# V3S.net
KiCad netlist of a schematic drawn in Altium Designer
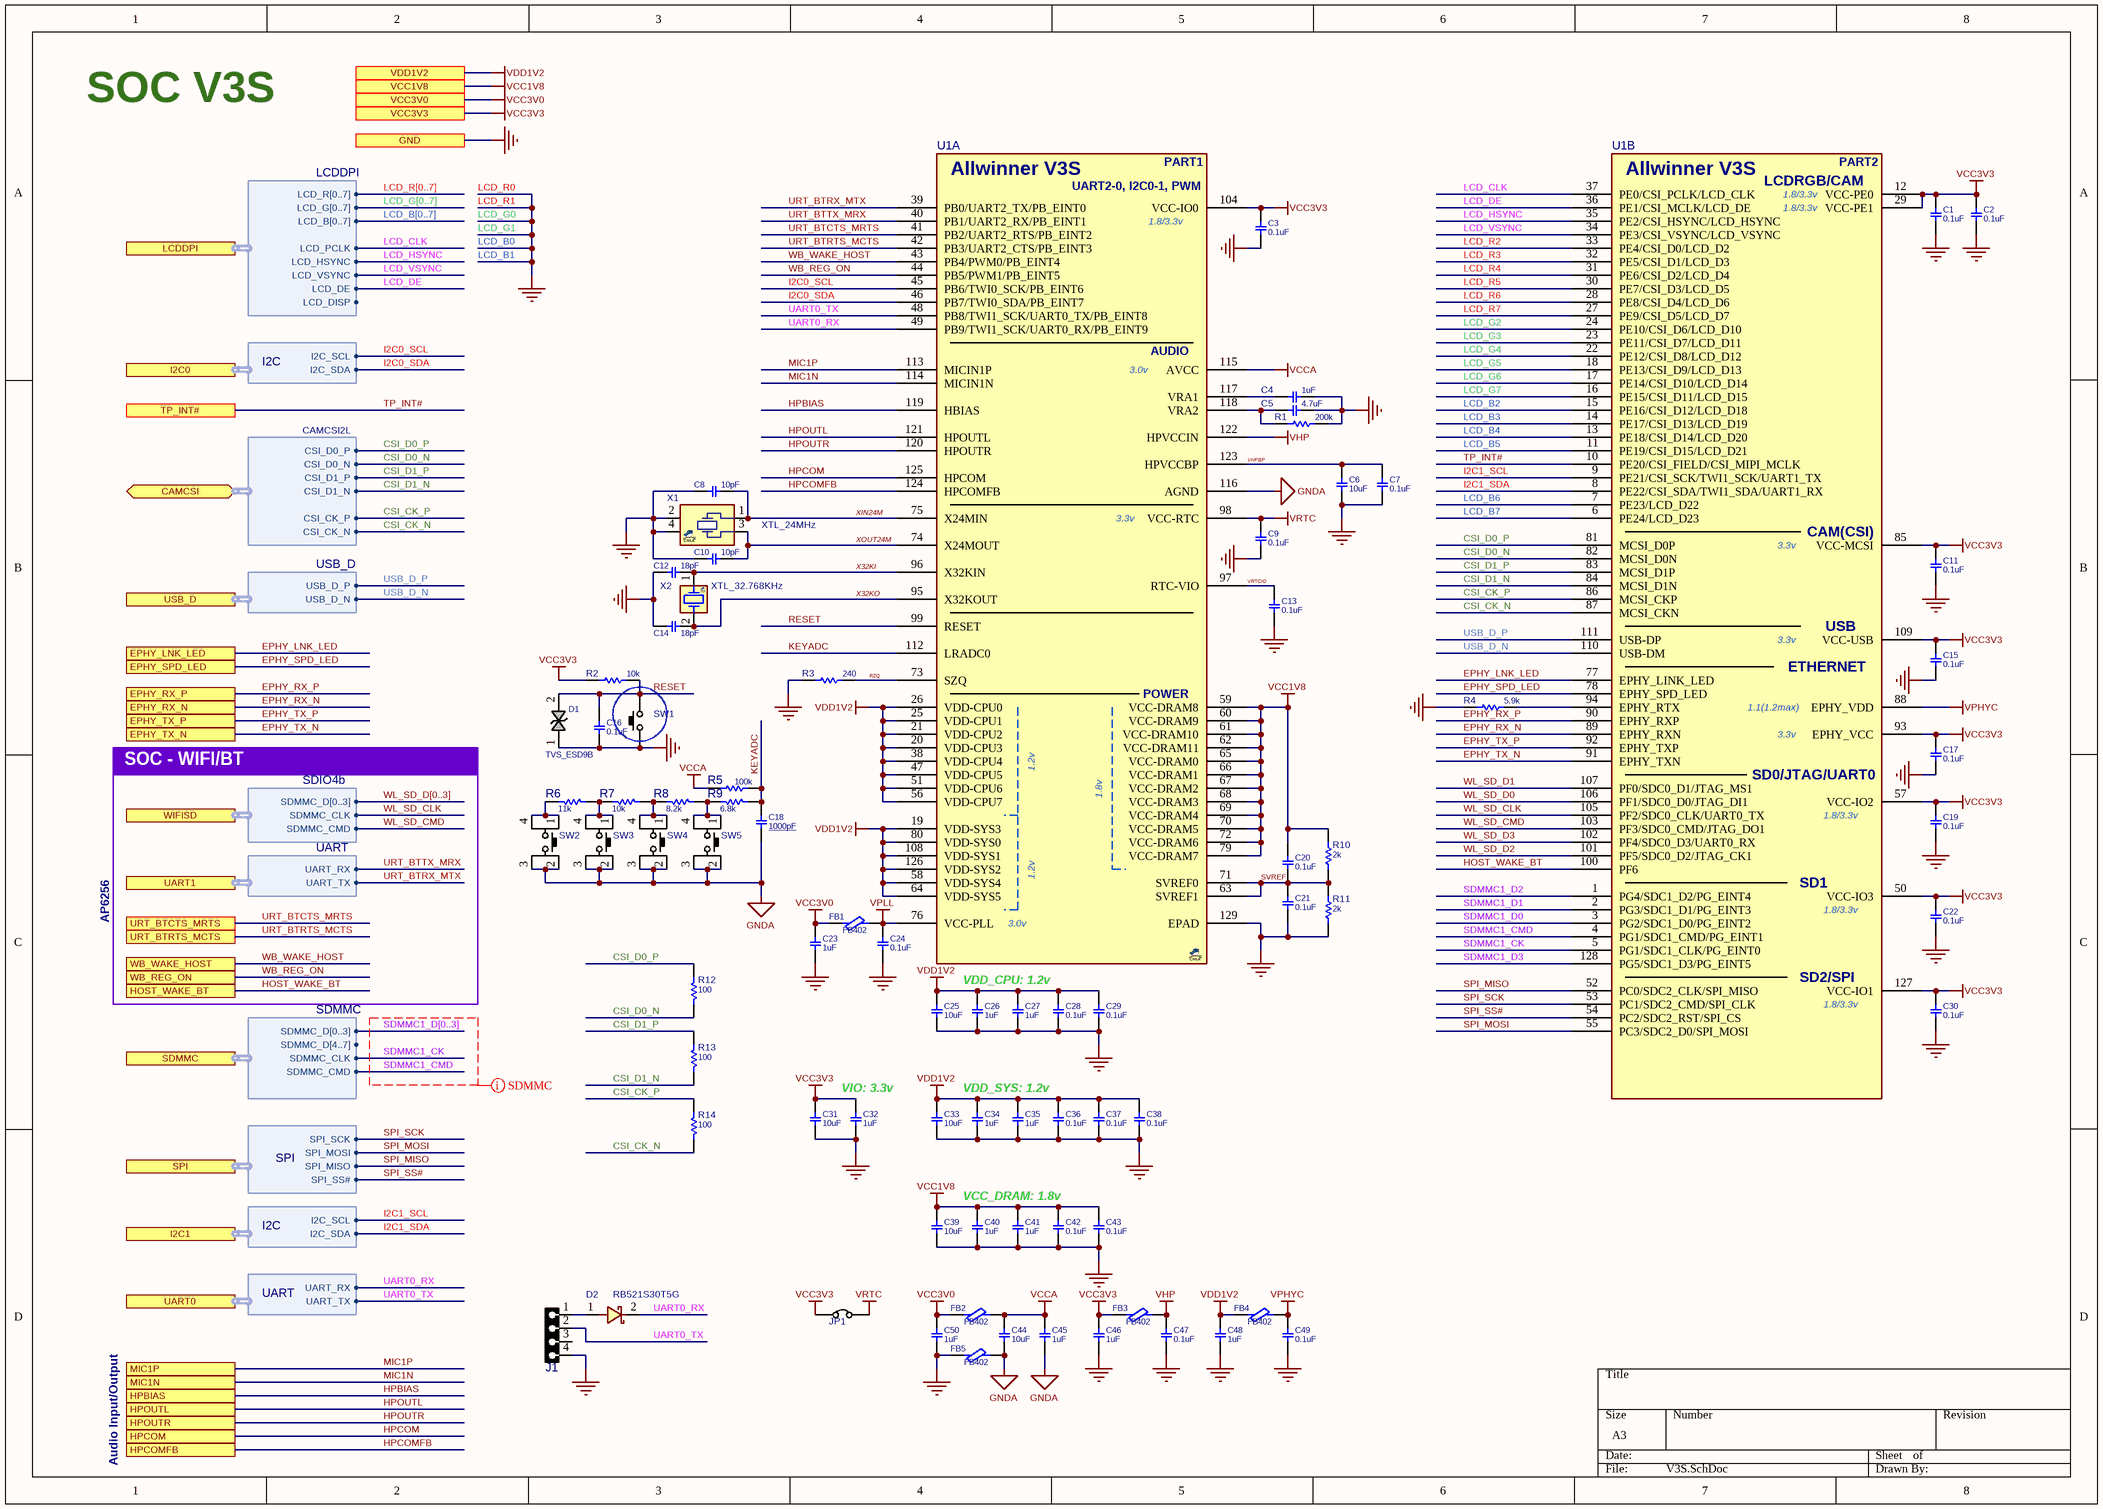
[diagram p0: V3S.SchDoc]

(export (version "E")
  (design (tool "Eeschema 10.0.6"))
  (components
    (comp (ref "C1")
      (value "0.1uF")
      (footprint "C0402")
      (description "CAP, MLCC")
      (fields (field (name "MANF_P#") "GRM155R71H104KE14D") (field (name "MANF") "Murata"))
      (libsource (lib "passive_smd") (part "CAP_SMD_MLCC"))
    )
    (comp (ref "C2")
      (value "0.1uF")
      (footprint "C0402")
      (description "CAP, MLCC")
      (fields (field (name "MANF_P#") "GRM155R71H104KE14D") (field (name "MANF") "Murata"))
      (libsource (lib "passive_smd") (part "CAP_SMD_MLCC"))
    )
    (comp (ref "C3")
      (value "0.1uF")
      (footprint "C0402")
      (description "CAP, MLCC")
      (fields (field (name "MANF_P#") "GRM155R71H104KE14D") (field (name "MANF") "Murata"))
      (libsource (lib "passive_smd") (part "CAP_SMD_MLCC"))
    )
    (comp (ref "C4")
      (value "1uF")
      (footprint "C0402")
      (description "CAP, MLCC")
      (fields (field (name "MANF_P#") "GMK105ABJ105KV-F") (field (name "MANF") "Taiyo Yuden"))
      (libsource (lib "passive_smd") (part "CAP_SMD_MLCC"))
    )
    (comp (ref "C5")
      (value "4.7uF")
      (footprint "C0402")
      (description "CAP, MLCC")
      (fields (field (name "MANF_P#") "LMK105BBJ475MVLF") (field (name "MANF") "Taiyo Yuden"))
      (libsource (lib "passive_smd") (part "CAP_SMD_MLCC"))
    )
    (comp (ref "C6")
      (value "10uF")
      (footprint "C0402")
      (description "CAP, MLCC")
      (fields (field (name "MANF_P#") "GRM155R60J106ME15") (field (name "MANF") "Murata"))
      (libsource (lib "mlcc_smd_passive") (part "CAP_SMD_MLCC"))
    )
    (comp (ref "C7")
      (value "0.1uF")
      (footprint "C0402")
      (description "CAP, MLCC")
      (fields (field (name "MANF_P#") "GRM155R71H104KE14D") (field (name "MANF") "Murata"))
      (libsource (lib "passive_smd") (part "CAP_SMD_MLCC"))
    )
    (comp (ref "C8")
      (value "10pF")
      (footprint "C0402")
      (description "CAP, MLCC")
      (fields (field (name "MANF_P#") "CC0402JRNPO9BN180") (field (name "MANF") "Yageo"))
      (libsource (lib "mlcc_smd_passive") (part "CAP_SMD_MLCC"))
    )
    (comp (ref "C9")
      (value "0.1uF")
      (footprint "C0402")
      (description "CAP, MLCC")
      (fields (field (name "MANF_P#") "GRM155R71H104KE14D") (field (name "MANF") "Murata"))
      (libsource (lib "passive_smd") (part "CAP_SMD_MLCC"))
    )
    (comp (ref "C10")
      (value "10pF")
      (footprint "C0402")
      (description "CAP, MLCC")
      (fields (field (name "MANF_P#") "CC0402JRNPO9BN180") (field (name "MANF") "Yageo"))
      (libsource (lib "mlcc_smd_passive") (part "CAP_SMD_MLCC"))
    )
    (comp (ref "C11")
      (value "0.1uF")
      (footprint "C0402")
      (description "CAP, MLCC")
      (fields (field (name "MANF_P#") "GRM155R71H104KE14D") (field (name "MANF") "Murata"))
      (libsource (lib "passive_smd") (part "CAP_SMD_MLCC"))
    )
    (comp (ref "C12")
      (value "18pF")
      (footprint "C0402")
      (description "CAP, MLCC")
      (fields (field (name "MANF_P#") "CC0402CRNPO9BN3R3") (field (name "MANF") "YAGEO"))
      (libsource (lib "passive_smd") (part "CAP_SMD_MLCC"))
    )
    (comp (ref "C13")
      (value "0.1uF")
      (footprint "C0402")
      (description "CAP, MLCC")
      (fields (field (name "MANF_P#") "GRM155R71H104KE14D") (field (name "MANF") "Murata"))
      (libsource (lib "passive_smd") (part "CAP_SMD_MLCC"))
    )
    (comp (ref "C14")
      (value "18pF")
      (footprint "C0402")
      (description "CAP, MLCC")
      (fields (field (name "MANF_P#") "CC0402CRNPO9BN3R3") (field (name "MANF") "YAGEO"))
      (libsource (lib "passive_smd") (part "CAP_SMD_MLCC"))
    )
    (comp (ref "C15")
      (value "0.1uF")
      (footprint "C0402")
      (description "CAP, MLCC")
      (fields (field (name "MANF_P#") "GRM155R71H104KE14D") (field (name "MANF") "Murata"))
      (libsource (lib "passive_smd") (part "CAP_SMD_MLCC"))
    )
    (comp (ref "C16")
      (value "0.1uF")
      (footprint "C0402")
      (description "CAP, MLCC")
      (fields (field (name "MANF_P#") "CL03A104KP3NNWC") (field (name "MANF") "Samsung"))
      (libsource (lib "passive_smd") (part "CAP_SMD_MLCC"))
    )
    (comp (ref "C17")
      (value "0.1uF")
      (footprint "C0402")
      (description "CAP, MLCC")
      (fields (field (name "MANF_P#") "GRM155R71H104KE14D") (field (name "MANF") "Murata"))
      (libsource (lib "passive_smd") (part "CAP_SMD_MLCC"))
    )
    (comp (ref "C18")
      (value "1000pF")
      (footprint "C0402")
      (description "CAP, MLCC")
      (fields (field (name "MANF_P#") "MANF_PART#"))
      (libsource (lib "passive_smd") (part "CAP_SMD_MLCC_0603"))
    )
    (comp (ref "C19")
      (value "0.1uF")
      (footprint "C0402")
      (description "CAP, MLCC")
      (fields (field (name "MANF_P#") "GRM155R71H104KE14D") (field (name "MANF") "Murata"))
      (libsource (lib "passive_smd") (part "CAP_SMD_MLCC"))
    )
    (comp (ref "C20")
      (value "0.1uF")
      (footprint "C0402")
      (description "CAP, MLCC")
      (fields (field (name "MANF_P#") "GRM155R71H104KE14D") (field (name "MANF") "Murata"))
      (libsource (lib "passive_smd") (part "CAP_SMD_MLCC"))
    )
    (comp (ref "C21")
      (value "0.1uF")
      (footprint "C0402")
      (description "CAP, MLCC")
      (fields (field (name "MANF_P#") "GRM155R71H104KE14D") (field (name "MANF") "Murata"))
      (libsource (lib "passive_smd") (part "CAP_SMD_MLCC"))
    )
    (comp (ref "C22")
      (value "0.1uF")
      (footprint "C0402")
      (description "CAP, MLCC")
      (fields (field (name "MANF_P#") "GRM155R71H104KE14D") (field (name "MANF") "Murata"))
      (libsource (lib "passive_smd") (part "CAP_SMD_MLCC"))
    )
    (comp (ref "C23")
      (value "1uF")
      (footprint "C0402")
      (description "CAP, MLCC")
      (fields (field (name "MANF_P#") "GMK105ABJ105KV-F") (field (name "MANF") "Taiyo Yuden"))
      (libsource (lib "passive_smd") (part "CAP_SMD_MLCC"))
    )
    (comp (ref "C24")
      (value "0.1uF")
      (footprint "C0402")
      (description "CAP, MLCC")
      (fields (field (name "MANF_P#") "GRM155R71H104KE14D") (field (name "MANF") "Murata"))
      (libsource (lib "passive_smd") (part "CAP_SMD_MLCC"))
    )
    (comp (ref "C25")
      (value "10uF")
      (footprint "C0402")
      (description "CAP, MLCC")
      (fields (field (name "MANF_P#") "GRM155R60J106ME15") (field (name "MANF") "Murata"))
      (libsource (lib "mlcc_smd_passive") (part "CAP_SMD_MLCC"))
    )
    (comp (ref "C26")
      (value "1uF")
      (footprint "C0402")
      (description "CAP, MLCC")
      (fields (field (name "MANF_P#") "GMK105ABJ105KV-F") (field (name "MANF") "Taiyo Yuden"))
      (libsource (lib "passive_smd") (part "CAP_SMD_MLCC"))
    )
    (comp (ref "C27")
      (value "1uF")
      (footprint "C0402")
      (description "CAP, MLCC")
      (fields (field (name "MANF_P#") "GMK105ABJ105KV-F") (field (name "MANF") "Taiyo Yuden"))
      (libsource (lib "passive_smd") (part "CAP_SMD_MLCC"))
    )
    (comp (ref "C28")
      (value "0.1uF")
      (footprint "C0402")
      (description "CAP, MLCC")
      (fields (field (name "MANF_P#") "GRM155R71H104KE14D") (field (name "MANF") "Murata"))
      (libsource (lib "passive_smd") (part "CAP_SMD_MLCC"))
    )
    (comp (ref "C29")
      (value "0.1uF")
      (footprint "C0402")
      (description "CAP, MLCC")
      (fields (field (name "MANF_P#") "GRM155R71H104KE14D") (field (name "MANF") "Murata"))
      (libsource (lib "passive_smd") (part "CAP_SMD_MLCC"))
    )
    (comp (ref "C30")
      (value "0.1uF")
      (footprint "C0402")
      (description "CAP, MLCC")
      (fields (field (name "MANF_P#") "GRM155R71H104KE14D") (field (name "MANF") "Murata"))
      (libsource (lib "passive_smd") (part "CAP_SMD_MLCC"))
    )
    (comp (ref "C31")
      (value "10uF")
      (footprint "C0402")
      (description "CAP, MLCC")
      (fields (field (name "MANF_P#") "GRM155R60J106ME15") (field (name "MANF") "Murata"))
      (libsource (lib "mlcc_smd_passive") (part "CAP_SMD_MLCC"))
    )
    (comp (ref "C32")
      (value "1uF")
      (footprint "C0402")
      (description "CAP, MLCC")
      (fields (field (name "MANF_P#") "GMK105ABJ105KV-F") (field (name "MANF") "Taiyo Yuden"))
      (libsource (lib "passive_smd") (part "CAP_SMD_MLCC"))
    )
    (comp (ref "C33")
      (value "10uF")
      (footprint "C0402")
      (description "CAP, MLCC")
      (fields (field (name "MANF_P#") "GRM155R60J106ME15") (field (name "MANF") "Murata"))
      (libsource (lib "mlcc_smd_passive") (part "CAP_SMD_MLCC"))
    )
    (comp (ref "C34")
      (value "1uF")
      (footprint "C0402")
      (description "CAP, MLCC")
      (fields (field (name "MANF_P#") "GMK105ABJ105KV-F") (field (name "MANF") "Taiyo Yuden"))
      (libsource (lib "passive_smd") (part "CAP_SMD_MLCC"))
    )
    (comp (ref "C35")
      (value "1uF")
      (footprint "C0402")
      (description "CAP, MLCC")
      (fields (field (name "MANF_P#") "GMK105ABJ105KV-F") (field (name "MANF") "Taiyo Yuden"))
      (libsource (lib "passive_smd") (part "CAP_SMD_MLCC"))
    )
    (comp (ref "C36")
      (value "0.1uF")
      (footprint "C0402")
      (description "CAP, MLCC")
      (fields (field (name "MANF_P#") "GRM155R71H104KE14D") (field (name "MANF") "Murata"))
      (libsource (lib "passive_smd") (part "CAP_SMD_MLCC"))
    )
    (comp (ref "C37")
      (value "0.1uF")
      (footprint "C0402")
      (description "CAP, MLCC")
      (fields (field (name "MANF_P#") "GRM155R71H104KE14D") (field (name "MANF") "Murata"))
      (libsource (lib "passive_smd") (part "CAP_SMD_MLCC"))
    )
    (comp (ref "C38")
      (value "0.1uF")
      (footprint "C0402")
      (description "CAP, MLCC")
      (fields (field (name "MANF_P#") "GRM155R71H104KE14D") (field (name "MANF") "Murata"))
      (libsource (lib "passive_smd") (part "CAP_SMD_MLCC"))
    )
    (comp (ref "C39")
      (value "10uF")
      (footprint "C0402")
      (description "CAP, MLCC")
      (fields (field (name "MANF_P#") "GRM155R60J106ME15") (field (name "MANF") "Murata"))
      (libsource (lib "mlcc_smd_passive") (part "CAP_SMD_MLCC"))
    )
    (comp (ref "C40")
      (value "1uF")
      (footprint "C0402")
      (description "CAP, MLCC")
      (fields (field (name "MANF_P#") "GMK105ABJ105KV-F") (field (name "MANF") "Taiyo Yuden"))
      (libsource (lib "passive_smd") (part "CAP_SMD_MLCC"))
    )
    (comp (ref "C41")
      (value "1uF")
      (footprint "C0402")
      (description "CAP, MLCC")
      (fields (field (name "MANF_P#") "GMK105ABJ105KV-F") (field (name "MANF") "Taiyo Yuden"))
      (libsource (lib "passive_smd") (part "CAP_SMD_MLCC"))
    )
    (comp (ref "C42")
      (value "0.1uF")
      (footprint "C0402")
      (description "CAP, MLCC")
      (fields (field (name "MANF_P#") "GRM155R71H104KE14D") (field (name "MANF") "Murata"))
      (libsource (lib "passive_smd") (part "CAP_SMD_MLCC"))
    )
    (comp (ref "C43")
      (value "0.1uF")
      (footprint "C0402")
      (description "CAP, MLCC")
      (fields (field (name "MANF_P#") "GRM155R71H104KE14D") (field (name "MANF") "Murata"))
      (libsource (lib "passive_smd") (part "CAP_SMD_MLCC"))
    )
    (comp (ref "C44")
      (value "10uF")
      (footprint "C0402")
      (description "CAP, MLCC")
      (fields (field (name "MANF_P#") "GRM155R60J106ME15") (field (name "MANF") "Murata"))
      (libsource (lib "mlcc_smd_passive") (part "CAP_SMD_MLCC"))
    )
    (comp (ref "C45")
      (value "1uF")
      (footprint "C0402")
      (description "CAP, MLCC")
      (fields (field (name "MANF_P#") "GMK105ABJ105KV-F") (field (name "MANF") "Taiyo Yuden"))
      (libsource (lib "passive_smd") (part "CAP_SMD_MLCC"))
    )
    (comp (ref "C46")
      (value "1uF")
      (footprint "C0402")
      (description "CAP, MLCC")
      (fields (field (name "MANF_P#") "GMK105ABJ105KV-F") (field (name "MANF") "Taiyo Yuden"))
      (libsource (lib "passive_smd") (part "CAP_SMD_MLCC"))
    )
    (comp (ref "C47")
      (value "0.1uF")
      (footprint "C0402")
      (description "CAP, MLCC")
      (fields (field (name "MANF_P#") "GRM155R71H104KE14D") (field (name "MANF") "Murata"))
      (libsource (lib "passive_smd") (part "CAP_SMD_MLCC"))
    )
    (comp (ref "C48")
      (value "1uF")
      (footprint "C0402")
      (description "CAP, MLCC")
      (fields (field (name "MANF_P#") "GMK105ABJ105KV-F") (field (name "MANF") "Taiyo Yuden"))
      (libsource (lib "passive_smd") (part "CAP_SMD_MLCC"))
    )
    (comp (ref "C49")
      (value "0.1uF")
      (footprint "C0402")
      (description "CAP, MLCC")
      (fields (field (name "MANF_P#") "GRM155R71H104KE14D") (field (name "MANF") "Murata"))
      (libsource (lib "passive_smd") (part "CAP_SMD_MLCC"))
    )
    (comp (ref "C50")
      (value "1uF")
      (footprint "C0402")
      (description "CAP, MLCC")
      (fields (field (name "MANF_P#") "GMK105ABJ105KV-F") (field (name "MANF") "Taiyo Yuden"))
      (libsource (lib "passive_smd") (part "CAP_SMD_MLCC"))
    )
    (comp (ref "D1")
      (value "TVS_ESD9B")
      (footprint "D_SOD923")
      (description "TVS, ESD PROTECT, Bidirectional")
      (fields (field (name "MANF_P#") "ESD9B3.3ST5G") (field (name "MANF") "ON"))
      (libsource (lib "protect_tvs_esd_fuse") (part "TVS_ESD9B3.3"))
    )
    (comp (ref "D2")
      (value "RB521S30T5G")
      (footprint "D_SOD523")
      (description "DIODE, SCHOTTKY")
      (fields (field (name "MANF") "DIODES"))
      (libsource (lib "diode") (part "DIODE_SMD_SCHOTTKY_1N5819"))
    )
    (comp (ref "FB1")
      (value "FB402")
      (footprint "L0402")
      (description "FERRITE_Bead, 0402, 0.5A, 200mOhm, 120@100MHz")
      (fields (field (name "MANF") "MURATA") (field (name "MANF_P#") "BLM15AG121SN1D"))
      (libsource (lib "emi_filter") (part "FBEAD_SMD_BLM15PD121"))
    )
    (comp (ref "FB2")
      (value "FB402")
      (footprint "L0402")
      (description "FERRITE_Bead, 0402, 0.5A, 200mOhm, 120@100MHz")
      (fields (field (name "MANF") "MURATA") (field (name "MANF_P#") "BLM15AG121SN1D"))
      (libsource (lib "emi_filter") (part "FBEAD_SMD_BLM15PD121"))
    )
    (comp (ref "FB3")
      (value "FB402")
      (footprint "L0402")
      (description "FERRITE_Bead, 0402, 0.5A, 200mOhm, 120@100MHz")
      (fields (field (name "MANF") "MURATA") (field (name "MANF_P#") "BLM15AG121SN1D"))
      (libsource (lib "emi_filter") (part "FBEAD_SMD_BLM15PD121"))
    )
    (comp (ref "FB4")
      (value "FB402")
      (footprint "L0402")
      (description "FERRITE_Bead, 0402, 0.5A, 200mOhm, 120@100MHz")
      (fields (field (name "MANF") "MURATA") (field (name "MANF_P#") "BLM15AG121SN1D"))
      (libsource (lib "emi_filter") (part "FBEAD_SMD_BLM15PD121"))
    )
    (comp (ref "FB5")
      (value "FB402")
      (footprint "L0402")
      (description "FERRITE_Bead, 0402, 0.5A, 200mOhm, 120@100MHz")
      (fields (field (name "MANF") "MURATA") (field (name "MANF_P#") "BLM15AG121SN1D"))
      (libsource (lib "emi_filter") (part "FBEAD_SMD_BLM15PD121"))
    )
    (comp (ref "J1")
      (value "HDR1X4")
      (footprint "HDR127MAG_4")
      (description "CONN, HEADER, Female, pitch: 1.27mm, 4POS")
      (libsource (lib "conn_header_1.27mm_st") (part "HDRMINI_F_1X4"))
    )
    (comp (ref "JP1")
      (value "JMPSOLDER")
      (footprint "JP_60X100")
      (description "JUMPER, HEADER 2PIN")
      (fields (field (name "MANF") "MANF") (field (name "MANF_P#") "MANF_P#"))
      (libsource (lib "test-tp_jumper") (part "JUMPER_SOLDER"))
    )
    (comp (ref "R1")
      (value "200k")
      (footprint "R0402")
      (description "RESISTOR, SMD")
      (libsource (lib "passive_res_smd") (part "RES_SMD"))
    )
    (comp (ref "R2")
      (value "10k")
      (footprint "R0402")
      (description "RESISTOR, SMD")
      (libsource (lib "passive_res_smd") (part "RES_SMD"))
    )
    (comp (ref "R3")
      (value "240")
      (footprint "R0402")
      (description "RESISTOR, SMD")
      (libsource (lib "passive_res_smd") (part "RES_SMD"))
    )
    (comp (ref "R4")
      (value "5.9k")
      (footprint "R0402")
      (description "RESISTOR, SMD")
      (libsource (lib "passive_res_smd") (part "RES_SMD"))
    )
    (comp (ref "R5")
      (value "100k")
      (footprint "R0402")
      (description "RESISTOR, SMD")
      (libsource (lib "passive_smd") (part "RES_SMD_0603"))
    )
    (comp (ref "R6")
      (value "11k")
      (footprint "R0402")
      (description "RESISTOR, SMD")
      (libsource (lib "passive_smd") (part "RES_SMD_0603"))
    )
    (comp (ref "R7")
      (value "10k")
      (footprint "R0402")
      (description "RESISTOR, SMD")
      (libsource (lib "passive_smd") (part "RES_SMD_0603"))
    )
    (comp (ref "R8")
      (value "8.2k")
      (footprint "R0402")
      (description "RESISTOR, SMD")
      (libsource (lib "passive_smd") (part "RES_SMD_0603"))
    )
    (comp (ref "R9")
      (value "6.8k")
      (footprint "R0402")
      (description "RESISTOR, SMD")
      (libsource (lib "passive_smd") (part "RES_SMD_0603"))
    )
    (comp (ref "R10")
      (value "2k")
      (footprint "R0402")
      (description "RESISTOR, SMD")
      (libsource (lib "passive_res_smd") (part "RES_SMD"))
    )
    (comp (ref "R11")
      (value "2k")
      (footprint "R0402")
      (description "RESISTOR, SMD")
      (libsource (lib "passive_res_smd") (part "RES_SMD"))
    )
    (comp (ref "R12")
      (value "100")
      (footprint "R0402")
      (description "RESISTOR, SMD")
      (libsource (lib "passive_res_smd") (part "RES_SMD"))
    )
    (comp (ref "R13")
      (value "100")
      (footprint "R0402")
      (description "RESISTOR, SMD")
      (libsource (lib "passive_res_smd") (part "RES_SMD"))
    )
    (comp (ref "R14")
      (value "100")
      (footprint "R0402")
      (description "RESISTOR, SMD")
      (libsource (lib "passive_res_smd") (part "RES_SMD"))
    )
    (comp (ref "SW1")
      (value "PUSHBUTTON")
      (footprint "SWPBS_SPST_3X2X1")
      (description "SWITCH, PUSH BUTTON, TACTILE, SMD, SPST, 3X2.5X1.2mm")
      (fields (field (name "MANF") "OMRON") (field (name "MANF_P#") "B3U-1000P"))
      (libsource (lib "switch_tact_PUSHB") (part "SWPBS_SPST_3X2_B3U-1000P"))
    )
    (comp (ref "SW2")
      (value "PUSHBUTTON")
      (footprint "SWPBS_SPDT_R_KMS")
      (description "SWITCH, PUSH BUTTON, TACTILE, THD, SPDT, RIGHT")
      (libsource (lib "switch_tact_PUSHB") (part "SWPBS_SPDT_R_CK"))
    )
    (comp (ref "SW3")
      (value "PUSHBUTTON")
      (footprint "SWPBS_SPDT_R_KMS")
      (description "SWITCH, PUSH BUTTON, TACTILE, THD, SPDT, RIGHT")
      (libsource (lib "switch_tact_PUSHB") (part "SWPBS_SPDT_R_CK"))
    )
    (comp (ref "SW4")
      (value "PUSHBUTTON")
      (footprint "SWPBS_SPDT_R_KMS")
      (description "SWITCH, PUSH BUTTON, TACTILE, THD, SPDT, RIGHT")
      (libsource (lib "switch_tact_PUSHB") (part "SWPBS_SPDT_R_CK"))
    )
    (comp (ref "SW5")
      (value "PUSHBUTTON")
      (footprint "SWPBS_SPDT_R_KMS")
      (description "SWITCH, PUSH BUTTON, TACTILE, THD, SPDT, RIGHT")
      (libsource (lib "switch_tact_PUSHB") (part "SWPBS_SPDT_R_CK"))
    )
    (comp (ref "U1")
      (value "Allwinner V3s")
      (footprint "QFG40_128T")
      (description "processor, Cortex-A7 1.2GHz w 512Mb DDR2")
      (fields (field (name "MANF") "Allwinner") (field (name "MANF_P#") "V3s"))
      (libsource (lib "processor_allwinner") (part "V3S_QFP128"))
    )
    (comp (ref "X1")
      (value "XTL_24MHz")
      (footprint "XTL_4_2016")
      (description "CRYSTAL")
      (fields (field (name "MANF") "Murata"))
      (libsource (lib "crystal") (part "XTL_4_40MHz_3225A"))
    )
    (comp (ref "X2")
      (value "XTL_32.768KHz")
      (footprint "XTL_2_1610")
      (description "Crystal")
      (fields (field (name "MANF_P#") "ABS05-32.768KHZ-9-T"))
      (libsource (lib "crystal") (part "XTL_2_32.768_3215A"))
    )
  )
  (nets
    (net (code "9") (name "/CSI_CK_N") (class "Default")
      (node (ref "R14") (pin "1") (pinfunction "1_1") (pintype "passive"))
      (node (ref "U1") (pin "87") (pinfunction "MCSI_CKN_87") (pintype "passive"))
    )
    (net (code "10") (name "/CSI_CK_P") (class "Default")
      (node (ref "R14") (pin "2") (pinfunction "2_2") (pintype "passive"))
      (node (ref "U1") (pin "86") (pinfunction "MCSI_CKP_86") (pintype "passive"))
    )
    (net (code "11") (name "/CSI_D0_N") (class "Default")
      (node (ref "R12") (pin "1") (pinfunction "1_1") (pintype "passive"))
      (node (ref "U1") (pin "82") (pinfunction "MCSI_D0N_82") (pintype "passive"))
    )
    (net (code "12") (name "/CSI_D0_P") (class "Default")
      (node (ref "R12") (pin "2") (pinfunction "2_2") (pintype "passive"))
      (node (ref "U1") (pin "81") (pinfunction "MCSI_D0P_81") (pintype "passive"))
    )
    (net (code "13") (name "/CSI_D1_N") (class "Default")
      (node (ref "R13") (pin "1") (pinfunction "1_1") (pintype "passive"))
      (node (ref "U1") (pin "84") (pinfunction "MCSI_D1N_84") (pintype "passive"))
    )
    (net (code "14") (name "/CSI_D1_P") (class "Default")
      (node (ref "R13") (pin "2") (pinfunction "2_2") (pintype "passive"))
      (node (ref "U1") (pin "83") (pinfunction "MCSI_D1P_83") (pintype "passive"))
    )
    (net (code "15") (name "/EPHY_LNK_LED") (class "Default")
      (node (ref "U1") (pin "77") (pinfunction "EPHY_LINK_LED_77") (pintype "passive"))
    )
    (net (code "16") (name "/EPHY_RX_N") (class "Default")
      (node (ref "U1") (pin "89") (pinfunction "EPHY_RXN_89") (pintype "passive"))
    )
    (net (code "17") (name "/EPHY_RX_P") (class "Default")
      (node (ref "U1") (pin "90") (pinfunction "EPHY_RXP_90") (pintype "passive"))
    )
    (net (code "18") (name "/EPHY_SPD_LED") (class "Default")
      (node (ref "U1") (pin "78") (pinfunction "EPHY_SPD_LED_78") (pintype "passive"))
    )
    (net (code "19") (name "/EPHY_TX_N") (class "Default")
      (node (ref "U1") (pin "91") (pinfunction "EPHY_TXN_91") (pintype "passive"))
    )
    (net (code "20") (name "/EPHY_TX_P") (class "Default")
      (node (ref "U1") (pin "92") (pinfunction "EPHY_TXP_92") (pintype "passive"))
    )
    (net (code "21") (name "/HOST_WAKE_BT") (class "Default")
      (node (ref "U1") (pin "100") (pinfunction "PF6_100") (pintype "passive"))
    )
    (net (code "22") (name "/HPBIAS") (class "Default")
      (node (ref "U1") (pin "119") (pinfunction "HBIAS_119") (pintype "passive"))
    )
    (net (code "23") (name "/HPCOM") (class "Default")
      (node (ref "U1") (pin "125") (pinfunction "HPCOM_125") (pintype "passive"))
    )
    (net (code "24") (name "/HPCOMFB") (class "Default")
      (node (ref "U1") (pin "124") (pinfunction "HPCOMFB_124") (pintype "passive"))
    )
    (net (code "25") (name "/HPOUTL") (class "Default")
      (node (ref "U1") (pin "121") (pinfunction "HPOUTL_121") (pintype "passive"))
    )
    (net (code "26") (name "/HPOUTR") (class "Default")
      (node (ref "U1") (pin "120") (pinfunction "HPOUTR_120") (pintype "passive"))
    )
    (net (code "27") (name "/I2C0_SCL") (class "Default")
      (node (ref "U1") (pin "45") (pinfunction "PB6/TWI0_SCK/PB_EINT6_45") (pintype "passive"))
    )
    (net (code "28") (name "/I2C0_SDA") (class "Default")
      (node (ref "U1") (pin "46") (pinfunction "PB7/TWI0_SDA/PB_EINT7_46") (pintype "passive"))
    )
    (net (code "29") (name "/I2C1_SCL") (class "Default")
      (node (ref "U1") (pin "9") (pinfunction "PE21/CSI_SCK/TWI1_SCK/UART1_TX_9") (pintype "passive"))
    )
    (net (code "30") (name "/I2C1_SDA") (class "Default")
      (node (ref "U1") (pin "8") (pinfunction "PE22/CSI_SDA/TWI1_SDA/UART1_RX_8") (pintype "passive"))
    )
    (net (code "31") (name "/KEYADC") (class "Default")
      (node (ref "C18") (pin "2") (pinfunction "2_2") (pintype "passive"))
      (node (ref "R5") (pin "1") (pinfunction "1_1") (pintype "passive"))
      (node (ref "R9") (pin "1") (pinfunction "1_1") (pintype "passive"))
      (node (ref "U1") (pin "112") (pinfunction "LRADC0_112") (pintype "passive"))
    )
    (net (code "32") (name "/LCD_B2") (class "Default")
      (node (ref "U1") (pin "15") (pinfunction "PE16/CSI_D12/LCD_D18_15") (pintype "passive"))
    )
    (net (code "33") (name "/LCD_B3") (class "Default")
      (node (ref "U1") (pin "14") (pinfunction "PE17/CSI_D13/LCD_D19_14") (pintype "passive"))
    )
    (net (code "34") (name "/LCD_B4") (class "Default")
      (node (ref "U1") (pin "13") (pinfunction "PE18/CSI_D14/LCD_D20_13") (pintype "passive"))
    )
    (net (code "35") (name "/LCD_B5") (class "Default")
      (node (ref "U1") (pin "11") (pinfunction "PE19/CSI_D15/LCD_D21_11") (pintype "passive"))
    )
    (net (code "36") (name "/LCD_B6") (class "Default")
      (node (ref "U1") (pin "7") (pinfunction "PE23/LCD_D22_7") (pintype "passive"))
    )
    (net (code "37") (name "/LCD_B7") (class "Default")
      (node (ref "U1") (pin "6") (pinfunction "PE24/LCD_D23_6") (pintype "passive"))
    )
    (net (code "39") (name "/LCD_CLK") (class "Default")
      (node (ref "U1") (pin "37") (pinfunction "PE0/CSI_PCLK/LCD_CLK_37") (pintype "passive"))
    )
    (net (code "40") (name "/LCD_DE") (class "Default")
      (node (ref "U1") (pin "36") (pinfunction "PE1/CSI_MCLK/LCD_DE_36") (pintype "passive"))
    )
    (net (code "41") (name "/LCD_G2") (class "Default")
      (node (ref "U1") (pin "24") (pinfunction "PE10/CSI_D6/LCD_D10_24") (pintype "passive"))
    )
    (net (code "42") (name "/LCD_G3") (class "Default")
      (node (ref "U1") (pin "23") (pinfunction "PE11/CSI_D7/LCD_D11_23") (pintype "passive"))
    )
    (net (code "43") (name "/LCD_G4") (class "Default")
      (node (ref "U1") (pin "22") (pinfunction "PE12/CSI_D8/LCD_D12_22") (pintype "passive"))
    )
    (net (code "44") (name "/LCD_G5") (class "Default")
      (node (ref "U1") (pin "18") (pinfunction "PE13/CSI_D9/LCD_D13_18") (pintype "passive"))
    )
    (net (code "45") (name "/LCD_G6") (class "Default")
      (node (ref "U1") (pin "17") (pinfunction "PE14/CSI_D10/LCD_D14_17") (pintype "passive"))
    )
    (net (code "46") (name "/LCD_G7") (class "Default")
      (node (ref "U1") (pin "16") (pinfunction "PE15/CSI_D11/LCD_D15_16") (pintype "passive"))
    )
    (net (code "48") (name "/LCD_HSYNC") (class "Default")
      (node (ref "U1") (pin "35") (pinfunction "PE2/CSI_HSYNC/LCD_HSYNC_35") (pintype "passive"))
    )
    (net (code "49") (name "/LCD_R2") (class "Default")
      (node (ref "U1") (pin "33") (pinfunction "PE4/CSI_D0/LCD_D2_33") (pintype "passive"))
    )
    (net (code "50") (name "/LCD_R3") (class "Default")
      (node (ref "U1") (pin "32") (pinfunction "PE5/CSI_D1/LCD_D3_32") (pintype "passive"))
    )
    (net (code "51") (name "/LCD_R4") (class "Default")
      (node (ref "U1") (pin "31") (pinfunction "PE6/CSI_D2/LCD_D4_31") (pintype "passive"))
    )
    (net (code "52") (name "/LCD_R5") (class "Default")
      (node (ref "U1") (pin "30") (pinfunction "PE7/CSI_D3/LCD_D5_30") (pintype "passive"))
    )
    (net (code "53") (name "/LCD_R6") (class "Default")
      (node (ref "U1") (pin "28") (pinfunction "PE8/CSI_D4/LCD_D6_28") (pintype "passive"))
    )
    (net (code "54") (name "/LCD_R7") (class "Default")
      (node (ref "U1") (pin "27") (pinfunction "PE9/CSI_D5/LCD_D7_27") (pintype "passive"))
    )
    (net (code "56") (name "/LCD_VSYNC") (class "Default")
      (node (ref "U1") (pin "34") (pinfunction "PE3/CSI_VSYNC/LCD_VSYNC_34") (pintype "passive"))
    )
    (net (code "57") (name "/MIC1N") (class "Default")
      (node (ref "U1") (pin "114") (pinfunction "MICIN1N_114") (pintype "passive"))
    )
    (net (code "58") (name "/MIC1P") (class "Default")
      (node (ref "U1") (pin "113") (pinfunction "MICIN1P_113") (pintype "passive"))
    )
    (net (code "59") (name "/RESET") (class "Default")
      (node (ref "C16") (pin "2") (pinfunction "2_2") (pintype "passive"))
      (node (ref "D1") (pin "2") (pinfunction "2_2") (pintype "passive"))
      (node (ref "R2") (pin "1") (pinfunction "1_1") (pintype "passive"))
      (node (ref "SW1") (pin "2") (pinfunction "P3_2") (pintype "passive"))
      (node (ref "U1") (pin "99") (pinfunction "RESET_99") (pintype "passive"))
    )
    (net (code "60") (name "/RZQ") (class "Default")
      (node (ref "R3") (pin "1") (pinfunction "1_1") (pintype "passive"))
      (node (ref "U1") (pin "73") (pinfunction "SZQ_73") (pintype "passive"))
    )
    (net (code "61") (name "/SDMMC1_CK") (class "Default")
      (node (ref "U1") (pin "5") (pinfunction "PG1/SDC1_CLK/PG_EINT0_5") (pintype "passive"))
    )
    (net (code "62") (name "/SDMMC1_CMD") (class "Default")
      (node (ref "U1") (pin "4") (pinfunction "PG1/SDC1_CMD/PG_EINT1_4") (pintype "passive"))
    )
    (net (code "63") (name "/SDMMC1_D0") (class "Default")
      (node (ref "U1") (pin "3") (pinfunction "PG2/SDC1_D0/PG_EINT2_3") (pintype "passive"))
    )
    (net (code "64") (name "/SDMMC1_D1") (class "Default")
      (node (ref "U1") (pin "2") (pinfunction "PG3/SDC1_D1/PG_EINT3_2") (pintype "passive"))
    )
    (net (code "65") (name "/SDMMC1_D2") (class "Default")
      (node (ref "U1") (pin "1") (pinfunction "PG4/SDC1_D2/PG_EINT4_1") (pintype "passive"))
    )
    (net (code "66") (name "/SDMMC1_D3") (class "Default")
      (node (ref "U1") (pin "128") (pinfunction "PG5/SDC1_D3/PG_EINT5_128") (pintype "passive"))
    )
    (net (code "68") (name "/SPI_MISO") (class "Default")
      (node (ref "U1") (pin "52") (pinfunction "PC0/SDC2_CLK/SPI_MISO_52") (pintype "passive"))
    )
    (net (code "69") (name "/SPI_MOSI") (class "Default")
      (node (ref "U1") (pin "55") (pinfunction "PC3/SDC2_D0/SPI_MOSI_55") (pintype "passive"))
    )
    (net (code "70") (name "/SPI_SCK") (class "Default")
      (node (ref "U1") (pin "53") (pinfunction "PC1/SDC2_CMD/SPI_CLK_53") (pintype "passive"))
    )
    (net (code "71") (name "/SPI_SS#") (class "Default")
      (node (ref "U1") (pin "54") (pinfunction "PC2/SDC2_RST/SPI_CS_54") (pintype "passive"))
    )
    (net (code "72") (name "/SVREF") (class "Default")
      (node (ref "C20") (pin "1") (pinfunction "1_1") (pintype "passive"))
      (node (ref "C21") (pin "2") (pinfunction "2_2") (pintype "passive"))
      (node (ref "R10") (pin "2") (pinfunction "2_2") (pintype "passive"))
      (node (ref "R11") (pin "1") (pinfunction "1_1") (pintype "passive"))
      (node (ref "U1") (pin "63") (pinfunction "SVREF1_63") (pintype "passive"))
      (node (ref "U1") (pin "71") (pinfunction "SVREF0_71") (pintype "passive"))
    )
    (net (code "73") (name "/TP_INT#") (class "Default")
      (node (ref "U1") (pin "10") (pinfunction "PE20/CSI_FIELD/CSI_MIPI_MCLK_10") (pintype "passive"))
    )
    (net (code "74") (name "/UART0_RX") (class "Default")
      (node (ref "D2") (pin "2") (pinfunction "2_2") (pintype "passive"))
      (node (ref "U1") (pin "49") (pinfunction "PB9/TWI1_SCK/UART0_RX/PB_EINT9_49") (pintype "passive"))
    )
    (net (code "75") (name "/UART0_TX") (class "Default")
      (node (ref "J1") (pin "2") (pinfunction "2_2") (pintype "passive"))
      (node (ref "U1") (pin "48") (pinfunction "PB8/TWI1_SCK/UART0_TX/PB_EINT8_48") (pintype "passive"))
    )
    (net (code "76") (name "/URT_BTCTS_MRTS") (class "Default")
      (node (ref "U1") (pin "41") (pinfunction "PB2/UART2_RTS/PB_EINT2_41") (pintype "passive"))
    )
    (net (code "77") (name "/URT_BTRTS_MCTS") (class "Default")
      (node (ref "U1") (pin "42") (pinfunction "PB3/UART2_CTS/PB_EINT3_42") (pintype "passive"))
    )
    (net (code "78") (name "/URT_BTRX_MTX") (class "Default")
      (node (ref "U1") (pin "39") (pinfunction "PB0/UART2_TX/PB_EINT0_39") (pintype "passive"))
    )
    (net (code "79") (name "/URT_BTTX_MRX") (class "Default")
      (node (ref "U1") (pin "40") (pinfunction "PB1/UART2_RX/PB_EINT1_40") (pintype "passive"))
    )
    (net (code "80") (name "/USB_D_N") (class "Default")
      (node (ref "U1") (pin "110") (pinfunction "USB-DM_110") (pintype "passive"))
    )
    (net (code "81") (name "/USB_D_P") (class "Default")
      (node (ref "U1") (pin "111") (pinfunction "USB-DP_111") (pintype "passive"))
    )
    (net (code "82") (name "/VHPBP") (class "Default")
      (node (ref "C6") (pin "1") (pinfunction "1_1") (pintype "passive"))
      (node (ref "C7") (pin "2") (pinfunction "2_2") (pintype "passive"))
      (node (ref "U1") (pin "123") (pinfunction "HPVCCBP_123") (pintype "passive"))
    )
    (net (code "83") (name "/VRTCIO") (class "Default")
      (node (ref "C13") (pin "2") (pinfunction "2_2") (pintype "passive"))
      (node (ref "U1") (pin "97") (pinfunction "RTC-VIO_97") (pintype "passive"))
    )
    (net (code "84") (name "/WB_REG_ON") (class "Default")
      (node (ref "U1") (pin "44") (pinfunction "PB5/PWM1/PB_EINT5_44") (pintype "passive"))
    )
    (net (code "85") (name "/WB_WAKE_HOST") (class "Default")
      (node (ref "U1") (pin "43") (pinfunction "PB4/PWM0/PB_EINT4_43") (pintype "passive"))
    )
    (net (code "86") (name "/WL_SD_CLK") (class "Default")
      (node (ref "U1") (pin "105") (pinfunction "PF2/SDC0_CLK/UART0_TX_105") (pintype "passive"))
    )
    (net (code "87") (name "/WL_SD_CMD") (class "Default")
      (node (ref "U1") (pin "103") (pinfunction "PF3/SDC0_CMD/JTAG_DO1_103") (pintype "passive"))
    )
    (net (code "88") (name "/WL_SD_D0") (class "Default")
      (node (ref "U1") (pin "106") (pinfunction "PF1/SDC0_D0/JTAG_DI1_106") (pintype "passive"))
    )
    (net (code "89") (name "/WL_SD_D1") (class "Default")
      (node (ref "U1") (pin "107") (pinfunction "PF0/SDC0_D1/JTAG_MS1_107") (pintype "passive"))
    )
    (net (code "90") (name "/WL_SD_D2") (class "Default")
      (node (ref "U1") (pin "101") (pinfunction "PF5/SDC0_D2/JTAG_CK1_101") (pintype "passive"))
    )
    (net (code "91") (name "/WL_SD_D3") (class "Default")
      (node (ref "U1") (pin "102") (pinfunction "PF4/SDC0_D3/UART0_RX_102") (pintype "passive"))
    )
    (net (code "93") (name "/X32KI") (class "Default")
      (node (ref "C12") (pin "2") (pinfunction "2_2") (pintype "passive"))
      (node (ref "U1") (pin "96") (pinfunction "X32KIN_96") (pintype "passive"))
      (node (ref "X2") (pin "1") (pinfunction "OSC1_1") (pintype "passive"))
    )
    (net (code "94") (name "/X32KO") (class "Default")
      (node (ref "C14") (pin "2") (pinfunction "2_2") (pintype "passive"))
      (node (ref "U1") (pin "95") (pinfunction "X32KOUT_95") (pintype "passive"))
      (node (ref "X2") (pin "2") (pinfunction "OSC2_2") (pintype "passive"))
    )
    (net (code "95") (name "/XIN24M") (class "Default")
      (node (ref "C8") (pin "1") (pinfunction "1_1") (pintype "passive"))
      (node (ref "U1") (pin "75") (pinfunction "X24MIN_75") (pintype "passive"))
      (node (ref "X1") (pin "1") (pinfunction "1_1") (pintype "passive"))
    )
    (net (code "96") (name "/XOUT24M") (class "Default")
      (node (ref "C10") (pin "1") (pinfunction "1_1") (pintype "passive"))
      (node (ref "U1") (pin "74") (pinfunction "X24MOUT_74") (pintype "passive"))
      (node (ref "X1") (pin "3") (pinfunction "2_3") (pintype "passive"))
    )
    (net (code "105") (name "GND") (class "Default")
      (node (ref "C1") (pin "1") (pinfunction "1_1") (pintype "passive"))
      (node (ref "C10") (pin "2") (pinfunction "2_2") (pintype "passive"))
      (node (ref "C11") (pin "1") (pinfunction "1_1") (pintype "passive"))
      (node (ref "C12") (pin "1") (pinfunction "1_1") (pintype "passive"))
      (node (ref "C13") (pin "1") (pinfunction "1_1") (pintype "passive"))
      (node (ref "C14") (pin "1") (pinfunction "1_1") (pintype "passive"))
      (node (ref "C15") (pin "1") (pinfunction "1_1") (pintype "passive"))
      (node (ref "C16") (pin "1") (pinfunction "1_1") (pintype "passive"))
      (node (ref "C17") (pin "1") (pinfunction "1_1") (pintype "passive"))
      (node (ref "C19") (pin "1") (pinfunction "1_1") (pintype "passive"))
      (node (ref "C2") (pin "1") (pinfunction "1_1") (pintype "passive"))
      (node (ref "C21") (pin "1") (pinfunction "1_1") (pintype "passive"))
      (node (ref "C22") (pin "1") (pinfunction "1_1") (pintype "passive"))
      (node (ref "C23") (pin "2") (pinfunction "2_2") (pintype "passive"))
      (node (ref "C24") (pin "1") (pinfunction "1_1") (pintype "passive"))
      (node (ref "C25") (pin "2") (pinfunction "2_2") (pintype "passive"))
      (node (ref "C26") (pin "2") (pinfunction "2_2") (pintype "passive"))
      (node (ref "C27") (pin "2") (pinfunction "2_2") (pintype "passive"))
      (node (ref "C28") (pin "1") (pinfunction "1_1") (pintype "passive"))
      (node (ref "C29") (pin "1") (pinfunction "1_1") (pintype "passive"))
      (node (ref "C3") (pin "1") (pinfunction "1_1") (pintype "passive"))
      (node (ref "C30") (pin "1") (pinfunction "1_1") (pintype "passive"))
      (node (ref "C31") (pin "2") (pinfunction "2_2") (pintype "passive"))
      (node (ref "C32") (pin "2") (pinfunction "2_2") (pintype "passive"))
      (node (ref "C33") (pin "2") (pinfunction "2_2") (pintype "passive"))
      (node (ref "C34") (pin "2") (pinfunction "2_2") (pintype "passive"))
      (node (ref "C35") (pin "2") (pinfunction "2_2") (pintype "passive"))
      (node (ref "C36") (pin "1") (pinfunction "1_1") (pintype "passive"))
      (node (ref "C37") (pin "1") (pinfunction "1_1") (pintype "passive"))
      (node (ref "C38") (pin "1") (pinfunction "1_1") (pintype "passive"))
      (node (ref "C39") (pin "2") (pinfunction "2_2") (pintype "passive"))
      (node (ref "C4") (pin "2") (pinfunction "2_2") (pintype "passive"))
      (node (ref "C40") (pin "2") (pinfunction "2_2") (pintype "passive"))
      (node (ref "C41") (pin "2") (pinfunction "2_2") (pintype "passive"))
      (node (ref "C42") (pin "1") (pinfunction "1_1") (pintype "passive"))
      (node (ref "C43") (pin "1") (pinfunction "1_1") (pintype "passive"))
      (node (ref "C46") (pin "2") (pinfunction "2_2") (pintype "passive"))
      (node (ref "C47") (pin "1") (pinfunction "1_1") (pintype "passive"))
      (node (ref "C48") (pin "2") (pinfunction "2_2") (pintype "passive"))
      (node (ref "C49") (pin "1") (pinfunction "1_1") (pintype "passive"))
      (node (ref "C5") (pin "2") (pinfunction "2_2") (pintype "passive"))
      (node (ref "C50") (pin "2") (pinfunction "2_2") (pintype "passive"))
      (node (ref "C6") (pin "2") (pinfunction "2_2") (pintype "passive"))
      (node (ref "C7") (pin "1") (pinfunction "1_1") (pintype "passive"))
      (node (ref "C8") (pin "2") (pinfunction "2_2") (pintype "passive"))
      (node (ref "C9") (pin "1") (pinfunction "1_1") (pintype "passive"))
      (node (ref "D1") (pin "1") (pinfunction "1_1") (pintype "passive"))
      (node (ref "FB5") (pin "1") (pinfunction "1_1") (pintype "passive"))
      (node (ref "J1") (pin "4") (pinfunction "4_4") (pintype "passive"))
      (node (ref "R1") (pin "2") (pinfunction "2_2") (pintype "passive"))
      (node (ref "R11") (pin "2") (pinfunction "2_2") (pintype "passive"))
      (node (ref "R3") (pin "2") (pinfunction "2_2") (pintype "passive"))
      (node (ref "R4") (pin "2") (pinfunction "2_2") (pintype "passive"))
      (node (ref "SW1") (pin "1") (pinfunction "P1_1") (pintype "passive"))
      (node (ref "U1") (pin "129") (pinfunction "EPAD_129") (pintype "passive"))
      (node (ref "X1") (pin "2") (pinfunction "2_2") (pintype "passive"))
      (node (ref "X1") (pin "4") (pinfunction "4_4") (pintype "passive"))
    )
    (net (code "106") (name "GNDA") (class "Default")
      (node (ref "C18") (pin "1") (pinfunction "1_1") (pintype "passive"))
      (node (ref "C44") (pin "2") (pinfunction "2_2") (pintype "passive"))
      (node (ref "C45") (pin "2") (pinfunction "2_2") (pintype "passive"))
      (node (ref "FB5") (pin "2") (pinfunction "2_2") (pintype "passive"))
      (node (ref "SW2") (pin "2") (pinfunction "2_2") (pintype "passive"))
      (node (ref "SW2") (pin "3") (pinfunction "3_3") (pintype "passive"))
      (node (ref "SW3") (pin "2") (pinfunction "2_2") (pintype "passive"))
      (node (ref "SW3") (pin "3") (pinfunction "3_3") (pintype "passive"))
      (node (ref "SW4") (pin "2") (pinfunction "2_2") (pintype "passive"))
      (node (ref "SW4") (pin "3") (pinfunction "3_3") (pintype "passive"))
      (node (ref "SW5") (pin "2") (pinfunction "2_2") (pintype "passive"))
      (node (ref "SW5") (pin "3") (pinfunction "3_3") (pintype "passive"))
      (node (ref "U1") (pin "116") (pinfunction "AGND_116") (pintype "passive"))
    )
    (net (code "107") (name "Net-(D2-Pad1)") (class "Default")
      (node (ref "D2") (pin "1") (pinfunction "1_1") (pintype "passive"))
      (node (ref "J1") (pin "1") (pinfunction "1_1") (pintype "passive"))
    )
    (net (code "108") (name "Net-(R6-Pad1)") (class "Default")
      (node (ref "R6") (pin "1") (pinfunction "1_1") (pintype "passive"))
      (node (ref "R7") (pin "2") (pinfunction "2_2") (pintype "passive"))
      (node (ref "SW3") (pin "1") (pinfunction "1_1") (pintype "passive"))
      (node (ref "SW3") (pin "4") (pinfunction "4_4") (pintype "passive"))
    )
    (net (code "109") (name "Net-(R6-Pad2)") (class "Default")
      (node (ref "R6") (pin "2") (pinfunction "2_2") (pintype "passive"))
      (node (ref "SW2") (pin "1") (pinfunction "1_1") (pintype "passive"))
      (node (ref "SW2") (pin "4") (pinfunction "4_4") (pintype "passive"))
    )
    (net (code "110") (name "Net-(R7-Pad1)") (class "Default")
      (node (ref "R7") (pin "1") (pinfunction "1_1") (pintype "passive"))
      (node (ref "R8") (pin "2") (pinfunction "2_2") (pintype "passive"))
      (node (ref "SW4") (pin "1") (pinfunction "1_1") (pintype "passive"))
      (node (ref "SW4") (pin "4") (pinfunction "4_4") (pintype "passive"))
    )
    (net (code "111") (name "Net-(R8-Pad1)") (class "Default")
      (node (ref "R8") (pin "1") (pinfunction "1_1") (pintype "passive"))
      (node (ref "R9") (pin "2") (pinfunction "2_2") (pintype "passive"))
      (node (ref "SW5") (pin "1") (pinfunction "1_1") (pintype "passive"))
      (node (ref "SW5") (pin "4") (pinfunction "4_4") (pintype "passive"))
    )
    (net (code "112") (name "Net-(U1A-VRA1)") (class "Default")
      (node (ref "C4") (pin "1") (pinfunction "1_1") (pintype "passive"))
      (node (ref "U1") (pin "117") (pinfunction "VRA1_117") (pintype "passive"))
    )
    (net (code "113") (name "Net-(U1A-VRA2)") (class "Default")
      (node (ref "C5") (pin "1") (pinfunction "1_1") (pintype "passive"))
      (node (ref "R1") (pin "1") (pinfunction "1_1") (pintype "passive"))
      (node (ref "U1") (pin "118") (pinfunction "VRA2_118") (pintype "passive"))
    )
    (net (code "114") (name "Net-(U1B-EPHY_RTX)") (class "Default")
      (node (ref "R4") (pin "1") (pinfunction "1_1") (pintype "passive"))
      (node (ref "U1") (pin "94") (pinfunction "EPHY_RTX_94") (pintype "passive"))
    )
    (net (code "115") (name "VCC1V8") (class "Default")
      (node (ref "C20") (pin "2") (pinfunction "2_2") (pintype "passive"))
      (node (ref "C39") (pin "1") (pinfunction "1_1") (pintype "passive"))
      (node (ref "C40") (pin "1") (pinfunction "1_1") (pintype "passive"))
      (node (ref "C41") (pin "1") (pinfunction "1_1") (pintype "passive"))
      (node (ref "C42") (pin "2") (pinfunction "2_2") (pintype "passive"))
      (node (ref "C43") (pin "2") (pinfunction "2_2") (pintype "passive"))
      (node (ref "R10") (pin "1") (pinfunction "1_1") (pintype "passive"))
      (node (ref "U1") (pin "59") (pinfunction "VCC-DRAM8_59") (pintype "passive"))
      (node (ref "U1") (pin "60") (pinfunction "VCC-DRAM9_60") (pintype "passive"))
      (node (ref "U1") (pin "61") (pinfunction "VCC-DRAM10_61") (pintype "passive"))
      (node (ref "U1") (pin "62") (pinfunction "VCC-DRAM11_62") (pintype "passive"))
      (node (ref "U1") (pin "65") (pinfunction "VCC-DRAM0_65") (pintype "passive"))
      (node (ref "U1") (pin "66") (pinfunction "VCC-DRAM1_66") (pintype "passive"))
      (node (ref "U1") (pin "67") (pinfunction "VCC-DRAM2_67") (pintype "passive"))
      (node (ref "U1") (pin "68") (pinfunction "VCC-DRAM3_68") (pintype "passive"))
      (node (ref "U1") (pin "69") (pinfunction "VCC-DRAM4_69") (pintype "passive"))
      (node (ref "U1") (pin "70") (pinfunction "VCC-DRAM5_70") (pintype "passive"))
      (node (ref "U1") (pin "72") (pinfunction "VCC-DRAM6_72") (pintype "passive"))
      (node (ref "U1") (pin "79") (pinfunction "VCC-DRAM7_79") (pintype "passive"))
    )
    (net (code "116") (name "VCC3V0") (class "Default")
      (node (ref "C23") (pin "1") (pinfunction "1_1") (pintype "passive"))
      (node (ref "C50") (pin "1") (pinfunction "1_1") (pintype "passive"))
      (node (ref "FB1") (pin "1") (pinfunction "1_1") (pintype "passive"))
      (node (ref "FB2") (pin "1") (pinfunction "1_1") (pintype "passive"))
    )
    (net (code "117") (name "VCC3V3") (class "Default")
      (node (ref "C1") (pin "2") (pinfunction "2_2") (pintype "passive"))
      (node (ref "C11") (pin "2") (pinfunction "2_2") (pintype "passive"))
      (node (ref "C15") (pin "2") (pinfunction "2_2") (pintype "passive"))
      (node (ref "C17") (pin "2") (pinfunction "2_2") (pintype "passive"))
      (node (ref "C19") (pin "2") (pinfunction "2_2") (pintype "passive"))
      (node (ref "C2") (pin "2") (pinfunction "2_2") (pintype "passive"))
      (node (ref "C22") (pin "2") (pinfunction "2_2") (pintype "passive"))
      (node (ref "C3") (pin "2") (pinfunction "2_2") (pintype "passive"))
      (node (ref "C30") (pin "2") (pinfunction "2_2") (pintype "passive"))
      (node (ref "C31") (pin "1") (pinfunction "1_1") (pintype "passive"))
      (node (ref "C32") (pin "1") (pinfunction "1_1") (pintype "passive"))
      (node (ref "C46") (pin "1") (pinfunction "1_1") (pintype "passive"))
      (node (ref "FB3") (pin "1") (pinfunction "1_1") (pintype "passive"))
      (node (ref "JP1") (pin "2") (pinfunction "2_2") (pintype "passive"))
      (node (ref "R2") (pin "2") (pinfunction "2_2") (pintype "passive"))
      (node (ref "U1") (pin "104") (pinfunction "VCC-IO0_104") (pintype "passive"))
      (node (ref "U1") (pin "109") (pinfunction "VCC-USB_109") (pintype "passive"))
      (node (ref "U1") (pin "12") (pinfunction "VCC-PE0_12") (pintype "passive"))
      (node (ref "U1") (pin "127") (pinfunction "VCC-IO1_127") (pintype "passive"))
      (node (ref "U1") (pin "29") (pinfunction "VCC-PE1_29") (pintype "passive"))
      (node (ref "U1") (pin "50") (pinfunction "VCC-IO3_50") (pintype "passive"))
      (node (ref "U1") (pin "57") (pinfunction "VCC-IO2_57") (pintype "passive"))
      (node (ref "U1") (pin "85") (pinfunction "VCC-MCSI_85") (pintype "passive"))
      (node (ref "U1") (pin "93") (pinfunction "EPHY_VCC_93") (pintype "passive"))
    )
    (net (code "118") (name "VCCA") (class "Default")
      (node (ref "C44") (pin "1") (pinfunction "1_1") (pintype "passive"))
      (node (ref "C45") (pin "1") (pinfunction "1_1") (pintype "passive"))
      (node (ref "FB2") (pin "2") (pinfunction "2_2") (pintype "passive"))
      (node (ref "R5") (pin "2") (pinfunction "2_2") (pintype "passive"))
      (node (ref "U1") (pin "115") (pinfunction "AVCC_115") (pintype "passive"))
    )
    (net (code "119") (name "VDD1V2") (class "Default")
      (node (ref "C25") (pin "1") (pinfunction "1_1") (pintype "passive"))
      (node (ref "C26") (pin "1") (pinfunction "1_1") (pintype "passive"))
      (node (ref "C27") (pin "1") (pinfunction "1_1") (pintype "passive"))
      (node (ref "C28") (pin "2") (pinfunction "2_2") (pintype "passive"))
      (node (ref "C29") (pin "2") (pinfunction "2_2") (pintype "passive"))
      (node (ref "C33") (pin "1") (pinfunction "1_1") (pintype "passive"))
      (node (ref "C34") (pin "1") (pinfunction "1_1") (pintype "passive"))
      (node (ref "C35") (pin "1") (pinfunction "1_1") (pintype "passive"))
      (node (ref "C36") (pin "2") (pinfunction "2_2") (pintype "passive"))
      (node (ref "C37") (pin "2") (pinfunction "2_2") (pintype "passive"))
      (node (ref "C38") (pin "2") (pinfunction "2_2") (pintype "passive"))
      (node (ref "C48") (pin "1") (pinfunction "1_1") (pintype "passive"))
      (node (ref "FB4") (pin "1") (pinfunction "1_1") (pintype "passive"))
      (node (ref "U1") (pin "108") (pinfunction "VDD-SYS1_108") (pintype "passive"))
      (node (ref "U1") (pin "126") (pinfunction "VDD-SYS2_126") (pintype "passive"))
      (node (ref "U1") (pin "19") (pinfunction "VDD-SYS3_19") (pintype "passive"))
      (node (ref "U1") (pin "20") (pinfunction "VDD-CPU3_20") (pintype "passive"))
      (node (ref "U1") (pin "21") (pinfunction "VDD-CPU2_21") (pintype "passive"))
      (node (ref "U1") (pin "25") (pinfunction "VDD-CPU1_25") (pintype "passive"))
      (node (ref "U1") (pin "26") (pinfunction "VDD-CPU0_26") (pintype "passive"))
      (node (ref "U1") (pin "38") (pinfunction "VDD-CPU4_38") (pintype "passive"))
      (node (ref "U1") (pin "47") (pinfunction "VDD-CPU5_47") (pintype "passive"))
      (node (ref "U1") (pin "51") (pinfunction "VDD-CPU6_51") (pintype "passive"))
      (node (ref "U1") (pin "56") (pinfunction "VDD-CPU7_56") (pintype "passive"))
      (node (ref "U1") (pin "58") (pinfunction "VDD-SYS4_58") (pintype "passive"))
      (node (ref "U1") (pin "64") (pinfunction "VDD-SYS5_64") (pintype "passive"))
      (node (ref "U1") (pin "80") (pinfunction "VDD-SYS0_80") (pintype "passive"))
    )
    (net (code "120") (name "VHP") (class "Default")
      (node (ref "C47") (pin "2") (pinfunction "2_2") (pintype "passive"))
      (node (ref "FB3") (pin "2") (pinfunction "2_2") (pintype "passive"))
      (node (ref "U1") (pin "122") (pinfunction "HPVCCIN_122") (pintype "passive"))
    )
    (net (code "121") (name "VPHYC") (class "Default")
      (node (ref "C49") (pin "2") (pinfunction "2_2") (pintype "passive"))
      (node (ref "FB4") (pin "2") (pinfunction "2_2") (pintype "passive"))
      (node (ref "U1") (pin "88") (pinfunction "EPHY_VDD_88") (pintype "passive"))
    )
    (net (code "122") (name "VPLL") (class "Default")
      (node (ref "C24") (pin "2") (pinfunction "2_2") (pintype "passive"))
      (node (ref "FB1") (pin "2") (pinfunction "2_2") (pintype "passive"))
      (node (ref "U1") (pin "76") (pinfunction "VCC-PLL_76") (pintype "passive"))
    )
    (net (code "123") (name "VRTC") (class "Default")
      (node (ref "C9") (pin "2") (pinfunction "2_2") (pintype "passive"))
      (node (ref "JP1") (pin "1") (pinfunction "1_1") (pintype "passive"))
      (node (ref "U1") (pin "98") (pinfunction "VCC-RTC_98") (pintype "passive"))
    )
    (net (code "124") (name "unconnected-(J1-Pad3)") (class "Default")
      (node (ref "J1") (pin "3") (pinfunction "3_3") (pintype "passive"))
    )
  )
)
